# HexBoard.net
KiCad netlist of a schematic drawn in EAGLE
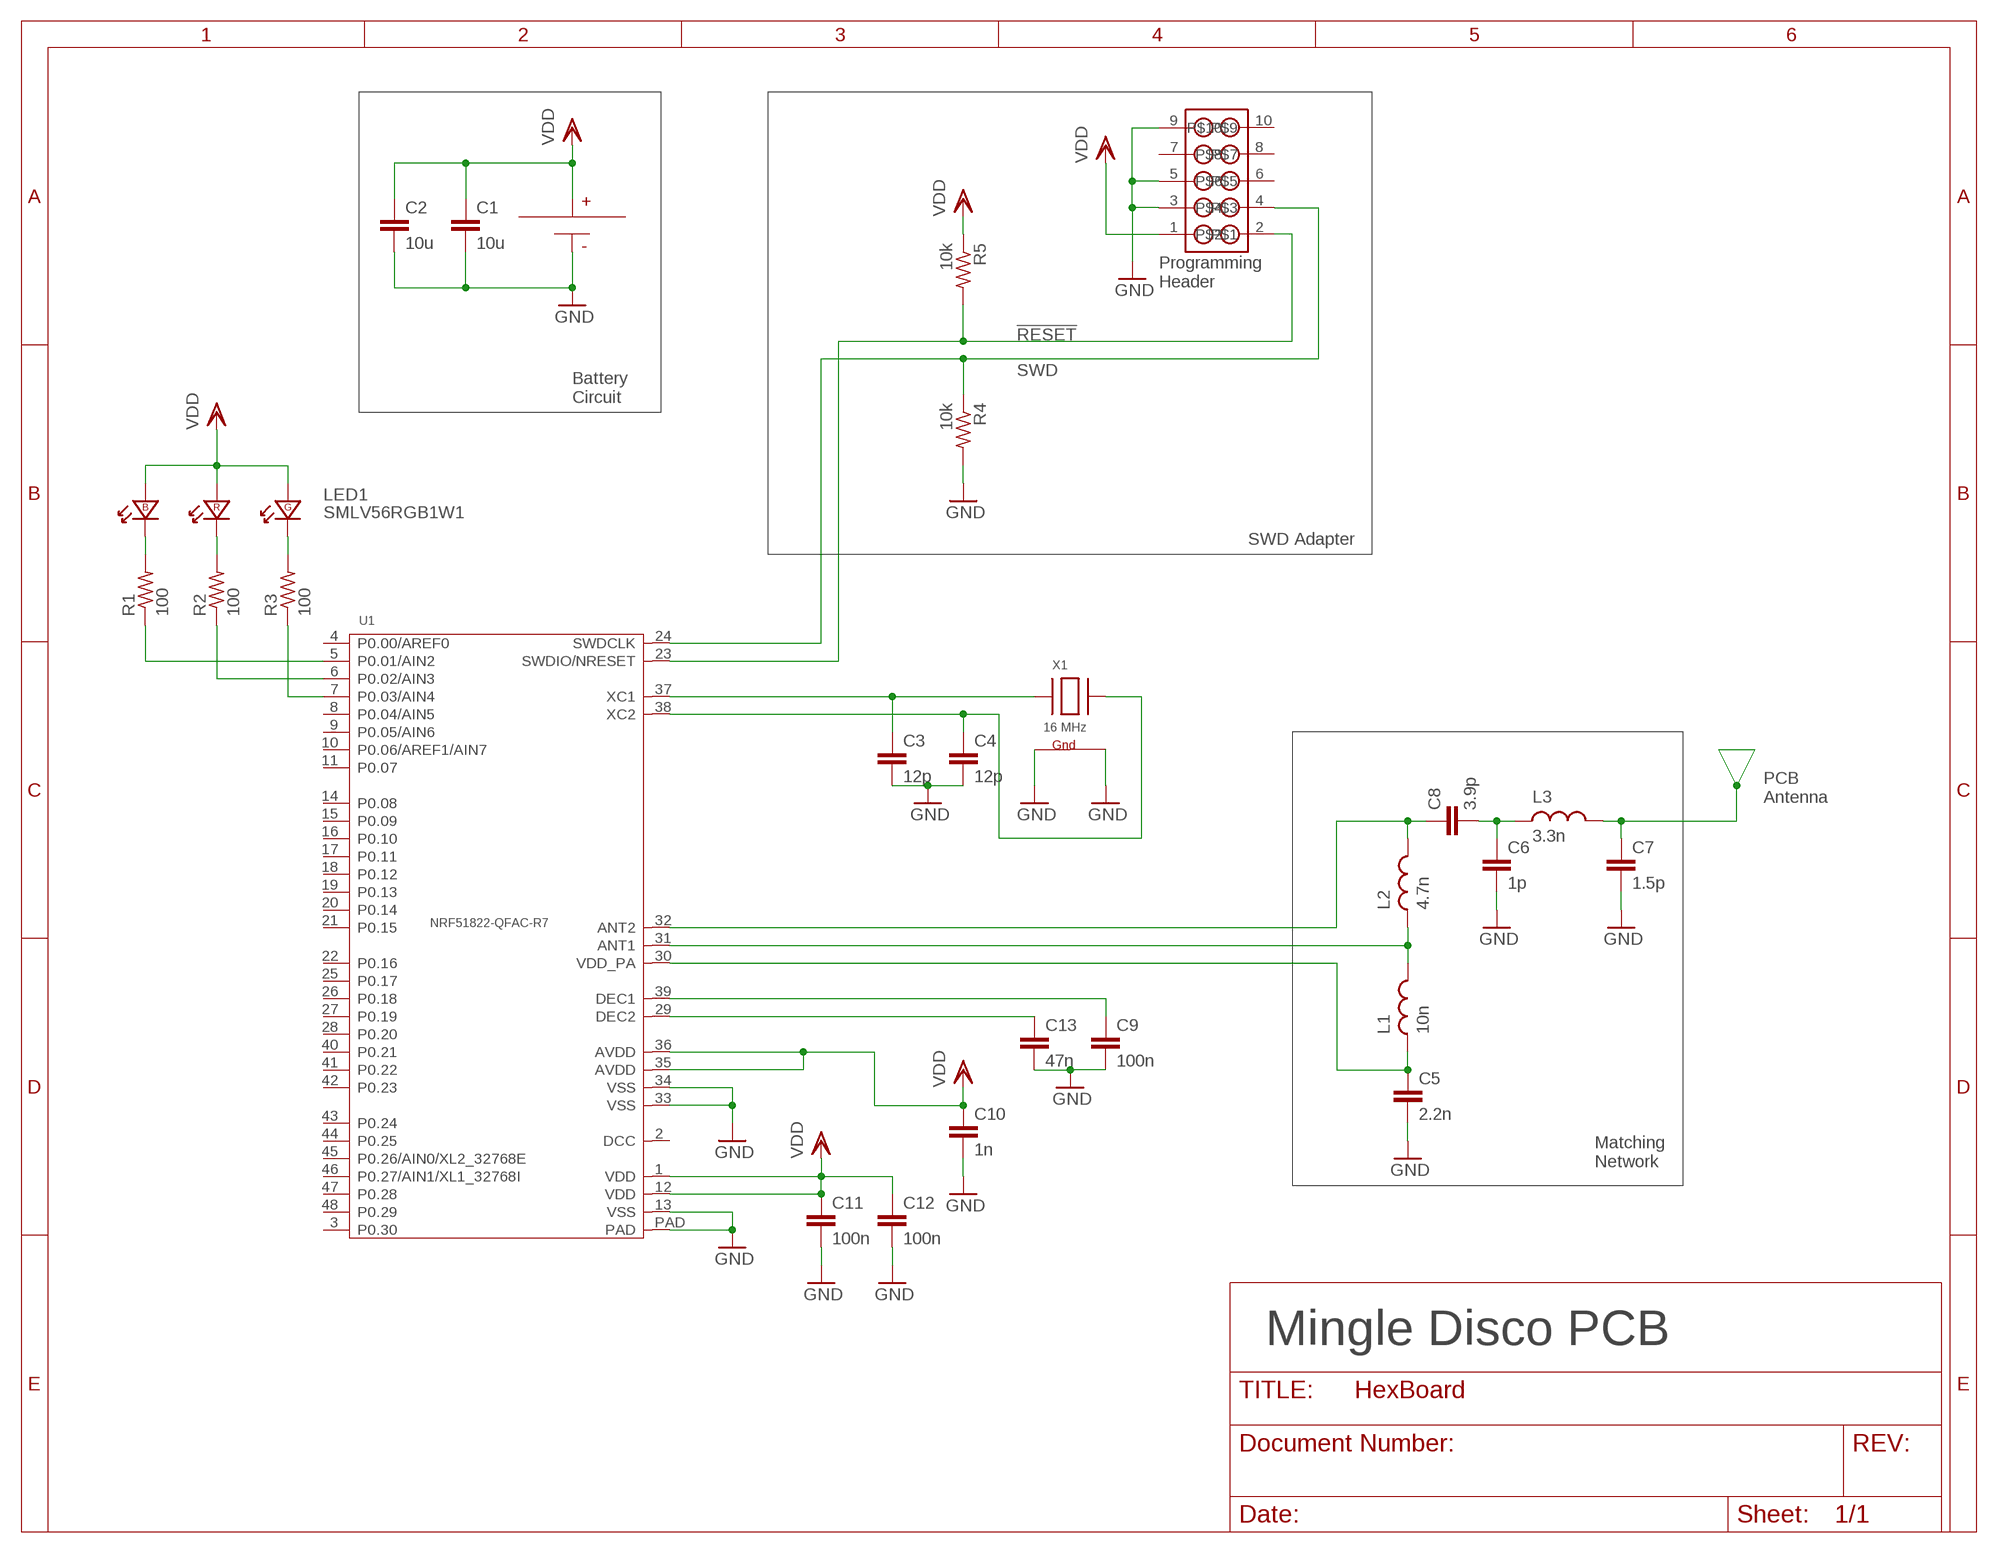
[diagram p0: schematic, sheet 1]

(export (version "E")
  (design (tool "Eeschema 10.0.6"))
  (components
    (comp (ref "B1")
      (value "CON-COINCEL-HOLDER-KEYSTONE-3012TR")
      (footprint "eagle-import:16MM-COINCELL-KEYSTONE")
      (libsource (lib "eagle-import") (part "CON-COINCEL-HOLDER-KEYSTONE-3012TR"))
    )
    (comp (ref "C1")
      (value "10u")
      (footprint "eagle-import:C0805")
      (libsource (lib "eagle-import") (part "C-EUC0805"))
    )
    (comp (ref "C2")
      (value "10u")
      (footprint "eagle-import:C0805")
      (libsource (lib "eagle-import") (part "C-EUC0805"))
    )
    (comp (ref "C3")
      (value "12p")
      (footprint "eagle-import:C0402")
      (libsource (lib "eagle-import") (part "C-EUC0402"))
    )
    (comp (ref "C4")
      (value "12p")
      (footprint "eagle-import:C0402")
      (libsource (lib "eagle-import") (part "C-EUC0402"))
    )
    (comp (ref "C5")
      (value "2.2n")
      (footprint "eagle-import:C0402")
      (libsource (lib "eagle-import") (part "C-EUC0402"))
    )
    (comp (ref "C6")
      (value "1p")
      (footprint "eagle-import:C0402")
      (libsource (lib "eagle-import") (part "C-EUC0402"))
    )
    (comp (ref "C7")
      (value "1.5p")
      (footprint "eagle-import:C0402")
      (libsource (lib "eagle-import") (part "C-EUC0402"))
    )
    (comp (ref "C8")
      (value "3.9p")
      (footprint "eagle-import:C0402")
      (libsource (lib "eagle-import") (part "C-EUC0402"))
    )
    (comp (ref "C9")
      (value "100n")
      (footprint "eagle-import:C0402")
      (libsource (lib "eagle-import") (part "C-EUC0402"))
    )
    (comp (ref "C10")
      (value "1n")
      (footprint "eagle-import:C0402")
      (libsource (lib "eagle-import") (part "C-EUC0402"))
    )
    (comp (ref "C11")
      (value "100n")
      (footprint "eagle-import:C0402")
      (libsource (lib "eagle-import") (part "C-EUC0402"))
    )
    (comp (ref "C12")
      (value "100n")
      (footprint "eagle-import:C0402")
      (libsource (lib "eagle-import") (part "C-EUC0402"))
    )
    (comp (ref "C13")
      (value "47n")
      (footprint "eagle-import:C0402")
      (libsource (lib "eagle-import") (part "C-EUC0402"))
    )
    (comp (ref "L1")
      (value "10n")
      (footprint "eagle-import:.0402-B-NOSILK")
      (libsource (lib "eagle-import") (part "L-US0402-B-NOSILK"))
    )
    (comp (ref "L2")
      (value "4.7n")
      (footprint "eagle-import:.0402-B-NOSILK")
      (libsource (lib "eagle-import") (part "L-US0402-B-NOSILK"))
    )
    (comp (ref "L3")
      (value "3.3n")
      (footprint "eagle-import:.0402-B-NOSILK")
      (libsource (lib "eagle-import") (part "L-US0402-B-NOSILK"))
    )
    (comp (ref "LED1")
      (value "SMLV56RGB1W1")
      (footprint "eagle-import:LED-3528")
      (libsource (lib "eagle-import") (part "LED-RGB-SEPARATE-3528"))
    )
    (comp (ref "R1")
      (value "100")
      (footprint "eagle-import:R0402")
      (libsource (lib "eagle-import") (part "R-US_R0402"))
    )
    (comp (ref "R2")
      (value "100")
      (footprint "eagle-import:R0402")
      (libsource (lib "eagle-import") (part "R-US_R0402"))
    )
    (comp (ref "R3")
      (value "100")
      (footprint "eagle-import:R0402")
      (libsource (lib "eagle-import") (part "R-US_R0402"))
    )
    (comp (ref "R4")
      (value "10k")
      (footprint "eagle-import:R0402")
      (libsource (lib "eagle-import") (part "R-US_R0402"))
    )
    (comp (ref "R5")
      (value "10k")
      (footprint "eagle-import:R0402")
      (libsource (lib "eagle-import") (part "R-US_R0402"))
    )
    (comp (ref "U$1")
      (value "HEADER.05\"PITCH")
      (footprint "eagle-import:HEADER.05_PITCH")
      (libsource (lib "eagle-import") (part "HEADER.05{dblquote}PITCH"))
    )
    (comp (ref "U1")
      (value "NRF51822-QFAC-R7")
      (footprint "eagle-import:QFN48-6X6MM")
      (libsource (lib "eagle-import") (part "NRF51822"))
    )
    (comp (ref "X1")
      (value "16 MHz")
      (footprint "eagle-import:TXC_CRYSTAL")
      (libsource (lib "eagle-import") (part "TXC-CRYSTAL"))
    )
  )
  (nets
    (net (code "1") (name "/SWD") (class "Default")
      (node (ref "R4") (pin "1") (pinfunction "1_1") (pintype "passive"))
      (node (ref "U$1") (pin "4") (pinfunction "P$4_4") (pintype "bidirectional"))
      (node (ref "U1") (pin "24") (pinfunction "SWDCLK_24") (pintype "bidirectional"))
    )
    (net (code "2") (name "/~{RESET}") (class "Default")
      (node (ref "R5") (pin "2") (pinfunction "2_2") (pintype "passive"))
      (node (ref "U$1") (pin "2") (pinfunction "P$2_2") (pintype "bidirectional"))
      (node (ref "U1") (pin "23") (pinfunction "SWDIO/NRESET_23") (pintype "bidirectional"))
    )
    (net (code "3") (name "GND") (class "Default")
      (node (ref "B1") (pin "NEG") (pinfunction "NEG_NEG") (pintype "power_in"))
      (node (ref "C1") (pin "2") (pinfunction "2_2") (pintype "passive"))
      (node (ref "C10") (pin "2") (pinfunction "2_2") (pintype "passive"))
      (node (ref "C11") (pin "2") (pinfunction "2_2") (pintype "passive"))
      (node (ref "C12") (pin "2") (pinfunction "2_2") (pintype "passive"))
      (node (ref "C13") (pin "2") (pinfunction "2_2") (pintype "passive"))
      (node (ref "C2") (pin "2") (pinfunction "2_2") (pintype "passive"))
      (node (ref "C3") (pin "2") (pinfunction "2_2") (pintype "passive"))
      (node (ref "C4") (pin "2") (pinfunction "2_2") (pintype "passive"))
      (node (ref "C5") (pin "2") (pinfunction "2_2") (pintype "passive"))
      (node (ref "C6") (pin "2") (pinfunction "2_2") (pintype "passive"))
      (node (ref "C7") (pin "2") (pinfunction "2_2") (pintype "passive"))
      (node (ref "C9") (pin "2") (pinfunction "2_2") (pintype "passive"))
      (node (ref "R4") (pin "2") (pinfunction "2_2") (pintype "passive"))
      (node (ref "U$1") (pin "3") (pinfunction "P$3_3") (pintype "bidirectional"))
      (node (ref "U$1") (pin "5") (pinfunction "P$5_5") (pintype "bidirectional"))
      (node (ref "U$1") (pin "9") (pinfunction "P$9_9") (pintype "bidirectional"))
      (node (ref "U1") (pin "13") (pinfunction "VSS_13") (pintype "bidirectional"))
      (node (ref "U1") (pin "33") (pinfunction "VSS_33") (pintype "bidirectional"))
      (node (ref "U1") (pin "34") (pinfunction "VSS_34") (pintype "bidirectional"))
      (node (ref "U1") (pin "PAD") (pinfunction "PAD_PAD") (pintype "bidirectional"))
      (node (ref "X1") (pin "2") (pinfunction "G1_2") (pintype "power_in"))
      (node (ref "X1") (pin "4") (pinfunction "G2_4") (pintype "power_in"))
    )
    (net (code "4") (name "Net-(C6-Pad1)") (class "Default")
      (node (ref "C6") (pin "1") (pinfunction "1_1") (pintype "passive"))
      (node (ref "C8") (pin "2") (pinfunction "2_2") (pintype "passive"))
      (node (ref "L3") (pin "1") (pinfunction "1_1") (pintype "passive"))
    )
    (net (code "5") (name "Net-(C7-Pad1)") (class "Default")
      (node (ref "C7") (pin "1") (pinfunction "1_1") (pintype "passive"))
      (node (ref "L3") (pin "2") (pinfunction "2_2") (pintype "passive"))
    )
    (net (code "6") (name "Net-(LED1A-K)") (class "Default")
      (node (ref "LED1") (pin "6") (pinfunction "K_6") (pintype "passive"))
      (node (ref "R1") (pin "2") (pinfunction "2_2") (pintype "passive"))
    )
    (net (code "7") (name "Net-(LED1B-K)") (class "Default")
      (node (ref "LED1") (pin "4") (pinfunction "K_4") (pintype "passive"))
      (node (ref "R3") (pin "2") (pinfunction "2_2") (pintype "passive"))
    )
    (net (code "8") (name "Net-(LED1C-K)") (class "Default")
      (node (ref "LED1") (pin "5") (pinfunction "K_5") (pintype "passive"))
      (node (ref "R2") (pin "2") (pinfunction "2_2") (pintype "passive"))
    )
    (net (code "9") (name "Net-(U1-ANT1)") (class "Default")
      (node (ref "L1") (pin "2") (pinfunction "2_2") (pintype "passive"))
      (node (ref "L2") (pin "1") (pinfunction "1_1") (pintype "passive"))
      (node (ref "U1") (pin "31") (pinfunction "ANT1_31") (pintype "bidirectional"))
    )
    (net (code "10") (name "Net-(U1-ANT2)") (class "Default")
      (node (ref "C8") (pin "1") (pinfunction "1_1") (pintype "passive"))
      (node (ref "L2") (pin "2") (pinfunction "2_2") (pintype "passive"))
      (node (ref "U1") (pin "32") (pinfunction "ANT2_32") (pintype "bidirectional"))
    )
    (net (code "11") (name "Net-(U1-DEC1)") (class "Default")
      (node (ref "C9") (pin "1") (pinfunction "1_1") (pintype "passive"))
      (node (ref "U1") (pin "39") (pinfunction "DEC1_39") (pintype "bidirectional"))
    )
    (net (code "12") (name "Net-(U1-DEC2)") (class "Default")
      (node (ref "C13") (pin "1") (pinfunction "1_1") (pintype "passive"))
      (node (ref "U1") (pin "29") (pinfunction "DEC2_29") (pintype "bidirectional"))
    )
    (net (code "13") (name "Net-(U1-P0.01{slash}AIN2)") (class "Default")
      (node (ref "R1") (pin "1") (pinfunction "1_1") (pintype "passive"))
      (node (ref "U1") (pin "5") (pinfunction "P0.01/AIN2_5") (pintype "bidirectional"))
    )
    (net (code "14") (name "Net-(U1-P0.02{slash}AIN3)") (class "Default")
      (node (ref "R2") (pin "1") (pinfunction "1_1") (pintype "passive"))
      (node (ref "U1") (pin "6") (pinfunction "P0.02/AIN3_6") (pintype "bidirectional"))
    )
    (net (code "15") (name "Net-(U1-P0.03{slash}AIN4)") (class "Default")
      (node (ref "R3") (pin "1") (pinfunction "1_1") (pintype "passive"))
      (node (ref "U1") (pin "7") (pinfunction "P0.03/AIN4_7") (pintype "bidirectional"))
    )
    (net (code "16") (name "Net-(U1-VDD_PA)") (class "Default")
      (node (ref "C5") (pin "1") (pinfunction "1_1") (pintype "passive"))
      (node (ref "L1") (pin "1") (pinfunction "1_1") (pintype "passive"))
      (node (ref "U1") (pin "30") (pinfunction "VDD_PA_30") (pintype "bidirectional"))
    )
    (net (code "17") (name "Net-(U1-XC1)") (class "Default")
      (node (ref "C3") (pin "1") (pinfunction "1_1") (pintype "passive"))
      (node (ref "U1") (pin "37") (pinfunction "XC1_37") (pintype "bidirectional"))
      (node (ref "X1") (pin "1") (pinfunction "X1_1") (pintype "bidirectional"))
    )
    (net (code "18") (name "Net-(U1-XC2)") (class "Default")
      (node (ref "C4") (pin "1") (pinfunction "1_1") (pintype "passive"))
      (node (ref "U1") (pin "38") (pinfunction "XC2_38") (pintype "bidirectional"))
      (node (ref "X1") (pin "3") (pinfunction "X2_3") (pintype "bidirectional"))
    )
    (net (code "19") (name "VDD") (class "Default")
      (node (ref "B1") (pin "POS@1") (pinfunction "POS_POS@1") (pintype "power_in"))
      (node (ref "B1") (pin "POS@2") (pinfunction "POS_POS@2") (pintype "power_in"))
      (node (ref "C1") (pin "1") (pinfunction "1_1") (pintype "passive"))
      (node (ref "C10") (pin "1") (pinfunction "1_1") (pintype "passive"))
      (node (ref "C11") (pin "1") (pinfunction "1_1") (pintype "passive"))
      (node (ref "C12") (pin "1") (pinfunction "1_1") (pintype "passive"))
      (node (ref "C2") (pin "1") (pinfunction "1_1") (pintype "passive"))
      (node (ref "LED1") (pin "1") (pinfunction "A_1") (pintype "passive"))
      (node (ref "LED1") (pin "2") (pinfunction "A_2") (pintype "passive"))
      (node (ref "LED1") (pin "3") (pinfunction "A_3") (pintype "passive"))
      (node (ref "R5") (pin "1") (pinfunction "1_1") (pintype "passive"))
      (node (ref "U$1") (pin "1") (pinfunction "P$1_1") (pintype "bidirectional"))
      (node (ref "U1") (pin "1") (pinfunction "VDD_1") (pintype "bidirectional"))
      (node (ref "U1") (pin "12") (pinfunction "VDD_12") (pintype "bidirectional"))
      (node (ref "U1") (pin "35") (pinfunction "AVDD_35") (pintype "bidirectional"))
      (node (ref "U1") (pin "36") (pinfunction "AVDD_36") (pintype "bidirectional"))
    )
    (net (code "20") (name "unconnected-(U$1-P$6-Pad6)") (class "Default")
      (node (ref "U$1") (pin "6") (pinfunction "P$6_6") (pintype "bidirectional"))
    )
    (net (code "21") (name "unconnected-(U$1-P$7-Pad7)") (class "Default")
      (node (ref "U$1") (pin "7") (pinfunction "P$7_7") (pintype "bidirectional"))
    )
    (net (code "22") (name "unconnected-(U$1-P$8-Pad8)") (class "Default")
      (node (ref "U$1") (pin "8") (pinfunction "P$8_8") (pintype "bidirectional"))
    )
    (net (code "23") (name "unconnected-(U$1-P$10-Pad10)") (class "Default")
      (node (ref "U$1") (pin "10") (pinfunction "P$10_10") (pintype "bidirectional"))
    )
    (net (code "24") (name "unconnected-(U1-DCC-Pad2)") (class "Default")
      (node (ref "U1") (pin "2") (pinfunction "DCC_2") (pintype "bidirectional"))
    )
    (net (code "25") (name "unconnected-(U1-P0.00{slash}AREF0-Pad4)") (class "Default")
      (node (ref "U1") (pin "4") (pinfunction "P0.00/AREF0_4") (pintype "bidirectional"))
    )
    (net (code "26") (name "unconnected-(U1-P0.04{slash}AIN5-Pad8)") (class "Default")
      (node (ref "U1") (pin "8") (pinfunction "P0.04/AIN5_8") (pintype "bidirectional"))
    )
    (net (code "27") (name "unconnected-(U1-P0.05{slash}AIN6-Pad9)") (class "Default")
      (node (ref "U1") (pin "9") (pinfunction "P0.05/AIN6_9") (pintype "bidirectional"))
    )
    (net (code "28") (name "unconnected-(U1-P0.06{slash}AREF1{slash}AIN7-Pad10)") (class "Default")
      (node (ref "U1") (pin "10") (pinfunction "P0.06/AREF1/AIN7_10") (pintype "bidirectional"))
    )
    (net (code "29") (name "unconnected-(U1-P0.07-Pad11)") (class "Default")
      (node (ref "U1") (pin "11") (pinfunction "P0.07_11") (pintype "bidirectional"))
    )
    (net (code "30") (name "unconnected-(U1-P0.08-Pad14)") (class "Default")
      (node (ref "U1") (pin "14") (pinfunction "P0.08_14") (pintype "bidirectional"))
    )
    (net (code "31") (name "unconnected-(U1-P0.09-Pad15)") (class "Default")
      (node (ref "U1") (pin "15") (pinfunction "P0.09_15") (pintype "bidirectional"))
    )
    (net (code "32") (name "unconnected-(U1-P0.10-Pad16)") (class "Default")
      (node (ref "U1") (pin "16") (pinfunction "P0.10_16") (pintype "bidirectional"))
    )
    (net (code "33") (name "unconnected-(U1-P0.11-Pad17)") (class "Default")
      (node (ref "U1") (pin "17") (pinfunction "P0.11_17") (pintype "bidirectional"))
    )
    (net (code "34") (name "unconnected-(U1-P0.12-Pad18)") (class "Default")
      (node (ref "U1") (pin "18") (pinfunction "P0.12_18") (pintype "bidirectional"))
    )
    (net (code "35") (name "unconnected-(U1-P0.13-Pad19)") (class "Default")
      (node (ref "U1") (pin "19") (pinfunction "P0.13_19") (pintype "bidirectional"))
    )
    (net (code "36") (name "unconnected-(U1-P0.14-Pad20)") (class "Default")
      (node (ref "U1") (pin "20") (pinfunction "P0.14_20") (pintype "bidirectional"))
    )
    (net (code "37") (name "unconnected-(U1-P0.15-Pad21)") (class "Default")
      (node (ref "U1") (pin "21") (pinfunction "P0.15_21") (pintype "bidirectional"))
    )
    (net (code "38") (name "unconnected-(U1-P0.16-Pad22)") (class "Default")
      (node (ref "U1") (pin "22") (pinfunction "P0.16_22") (pintype "bidirectional"))
    )
    (net (code "39") (name "unconnected-(U1-P0.17-Pad25)") (class "Default")
      (node (ref "U1") (pin "25") (pinfunction "P0.17_25") (pintype "bidirectional"))
    )
    (net (code "40") (name "unconnected-(U1-P0.18-Pad26)") (class "Default")
      (node (ref "U1") (pin "26") (pinfunction "P0.18_26") (pintype "bidirectional"))
    )
    (net (code "41") (name "unconnected-(U1-P0.19-Pad27)") (class "Default")
      (node (ref "U1") (pin "27") (pinfunction "P0.19_27") (pintype "bidirectional"))
    )
    (net (code "42") (name "unconnected-(U1-P0.20-Pad28)") (class "Default")
      (node (ref "U1") (pin "28") (pinfunction "P0.20_28") (pintype "bidirectional"))
    )
    (net (code "43") (name "unconnected-(U1-P0.21-Pad40)") (class "Default")
      (node (ref "U1") (pin "40") (pinfunction "P0.21_40") (pintype "bidirectional"))
    )
    (net (code "44") (name "unconnected-(U1-P0.22-Pad41)") (class "Default")
      (node (ref "U1") (pin "41") (pinfunction "P0.22_41") (pintype "bidirectional"))
    )
    (net (code "45") (name "unconnected-(U1-P0.23-Pad42)") (class "Default")
      (node (ref "U1") (pin "42") (pinfunction "P0.23_42") (pintype "bidirectional"))
    )
    (net (code "46") (name "unconnected-(U1-P0.24-Pad43)") (class "Default")
      (node (ref "U1") (pin "43") (pinfunction "P0.24_43") (pintype "bidirectional"))
    )
    (net (code "47") (name "unconnected-(U1-P0.25-Pad44)") (class "Default")
      (node (ref "U1") (pin "44") (pinfunction "P0.25_44") (pintype "bidirectional"))
    )
    (net (code "48") (name "unconnected-(U1-P0.26{slash}AIN0{slash}XL2_32768E-Pad45)") (class "Default")
      (node (ref "U1") (pin "45") (pinfunction "P0.26/AIN0/XL2_32768E_45") (pintype "bidirectional"))
    )
    (net (code "49") (name "unconnected-(U1-P0.27{slash}AIN1{slash}XL1_32768I-Pad46)") (class "Default")
      (node (ref "U1") (pin "46") (pinfunction "P0.27/AIN1/XL1_32768I_46") (pintype "bidirectional"))
    )
    (net (code "50") (name "unconnected-(U1-P0.28-Pad47)") (class "Default")
      (node (ref "U1") (pin "47") (pinfunction "P0.28_47") (pintype "bidirectional"))
    )
    (net (code "51") (name "unconnected-(U1-P0.29-Pad48)") (class "Default")
      (node (ref "U1") (pin "48") (pinfunction "P0.29_48") (pintype "bidirectional"))
    )
    (net (code "52") (name "unconnected-(U1-P0.30-Pad3)") (class "Default")
      (node (ref "U1") (pin "3") (pinfunction "P0.30_3") (pintype "bidirectional"))
    )
  )
)
